# connector_temp.net
KiCad netlist of a schematic drawn in Altium Designer
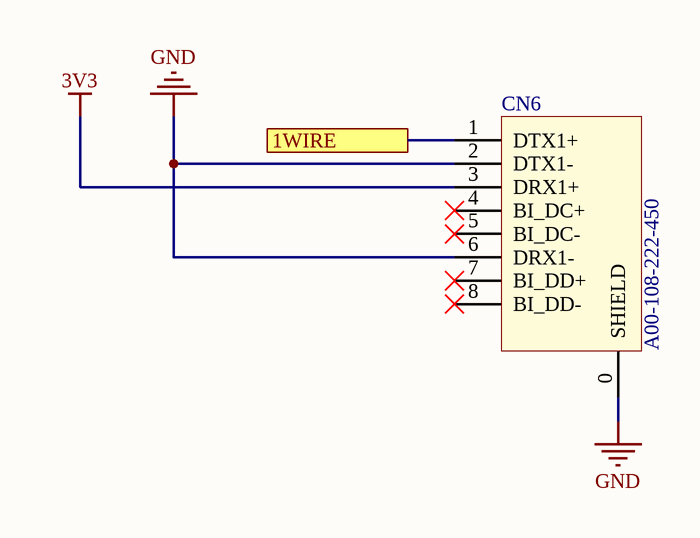
[diagram p0: connector_temp.SchDoc]

(export (version "E")
  (design (tool "Eeschema 10.0.6"))
  (components
    (comp (ref "CN6")
      (value "CONN_RJ45_TOP_A00-108-222-450")
      (footprint "RJ45 TOP ENTRY EDAC A00-108-222-450")
      (description "CONN, RJ-45, 1-PORT, 8-POS, VERT, 0.76um GOLD, TH")
      (fields (field (name "MFG") "EDAC Inc") (field (name "MFG P/N") "A00-108-222-450"))
      (libsource (lib "AltiumReleaseLibDB") (part "CONN_RJ45_TOP_A00-108-222-450"))
    )
  )
  (nets
    (net (code "1") (name "/1WIRE") (class "Default")
      (node (ref "CN6") (pin "1") (pinfunction "DTX1+_1") (pintype "passive"))
    )
    (net (code "2") (name "3V3") (class "Default")
      (node (ref "CN6") (pin "3") (pinfunction "DRX1+_3") (pintype "passive"))
    )
    (net (code "3") (name "GND") (class "Default")
      (node (ref "CN6") (pin "0") (pinfunction "SHIELD_0") (pintype "passive"))
      (node (ref "CN6") (pin "2") (pinfunction "DTX1-_2") (pintype "passive"))
      (node (ref "CN6") (pin "6") (pinfunction "DRX1-_6") (pintype "passive"))
    )
    (net (code "4") (name "unconnected-(CN6-BI_DC+-Pad4)") (class "Default")
      (node (ref "CN6") (pin "4") (pinfunction "BI_DC+_4") (pintype "passive+no_connect"))
    )
    (net (code "5") (name "unconnected-(CN6-BI_DC--Pad5)") (class "Default")
      (node (ref "CN6") (pin "5") (pinfunction "BI_DC-_5") (pintype "passive+no_connect"))
    )
    (net (code "6") (name "unconnected-(CN6-BI_DD+-Pad7)") (class "Default")
      (node (ref "CN6") (pin "7") (pinfunction "BI_DD+_7") (pintype "passive+no_connect"))
    )
    (net (code "7") (name "unconnected-(CN6-BI_DD--Pad8)") (class "Default")
      (node (ref "CN6") (pin "8") (pinfunction "BI_DD-_8") (pintype "passive+no_connect"))
    )
  )
)
